# tweeq-STAMP_I2C_PRESSURE_BMP180_v1.net
KiCad netlist of a schematic drawn in EAGLE
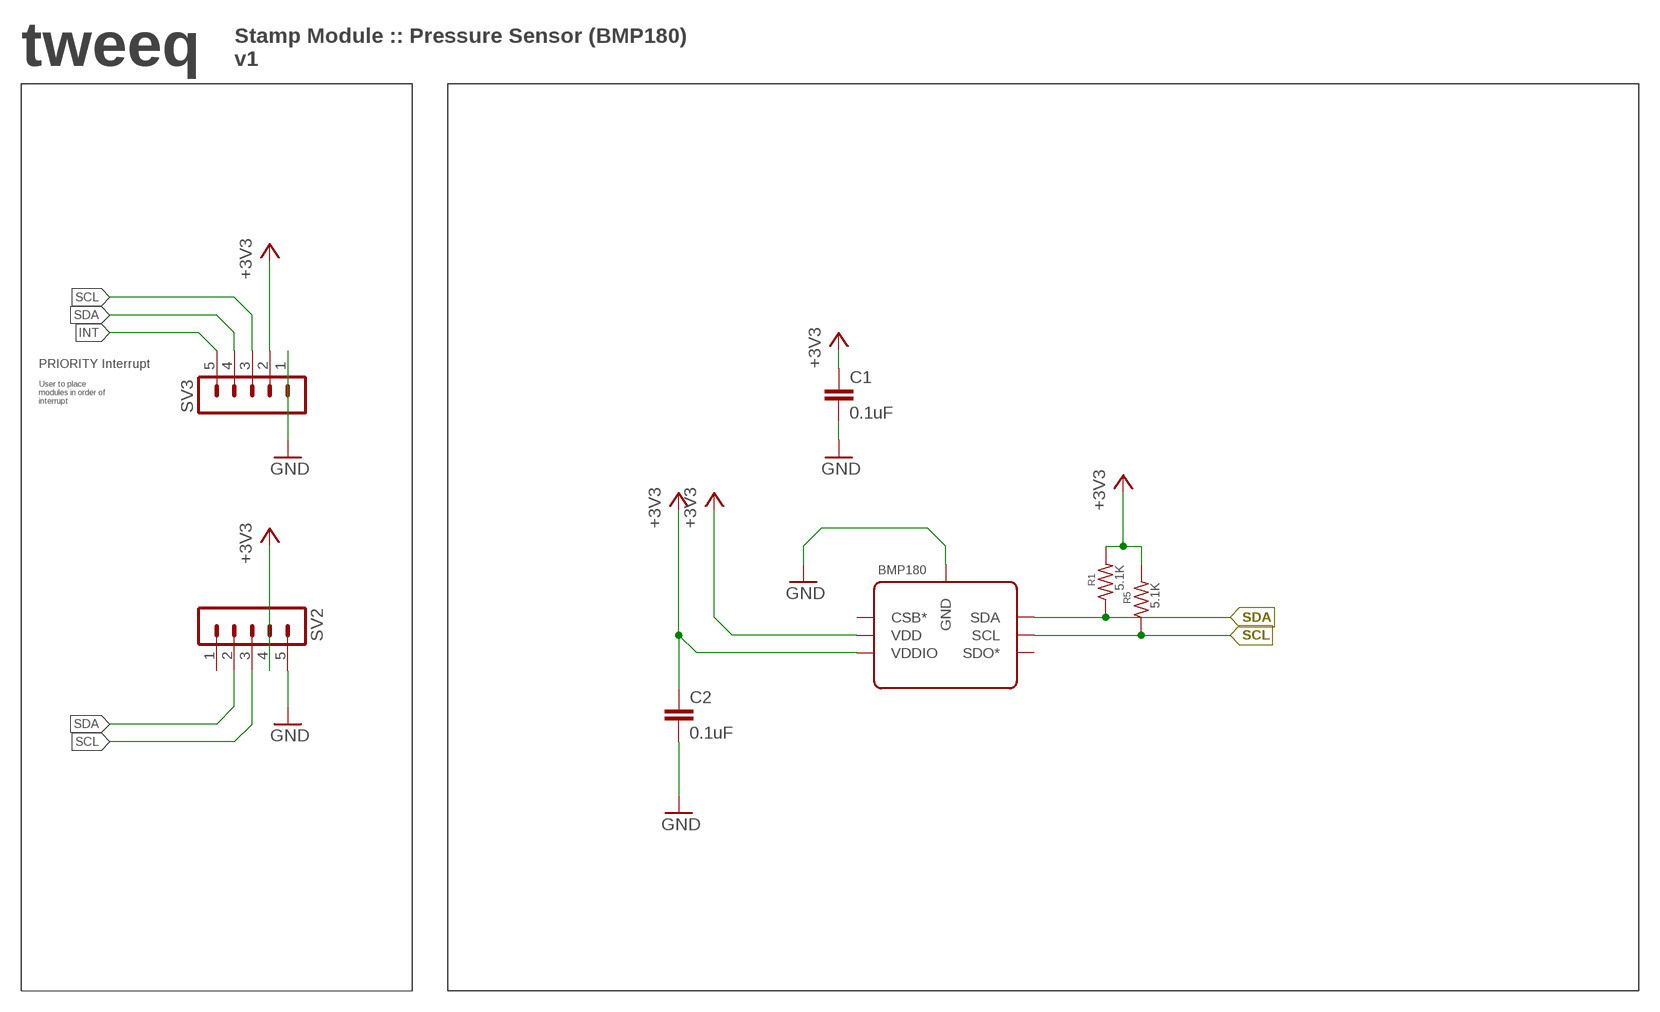
[diagram p0: schematic, sheet 1]

(export (version "E")
  (design (tool "Eeschema 10.0.6"))
  (components
    (comp (ref "BMP180")
      (value "BMP180")
      (footprint "eagle-import:LGA-7PIN")
      (libsource (lib "eagle-import") (part "BMP180"))
    )
    (comp (ref "C1")
      (value "0.1uF")
      (footprint "eagle-import:C0402K")
      (libsource (lib "eagle-import") (part "C-EUC0402K"))
    )
    (comp (ref "C2")
      (value "0.1uF")
      (footprint "eagle-import:C0402K")
      (libsource (lib "eagle-import") (part "C-EUC0402K"))
    )
    (comp (ref "R1")
      (value "5.1K")
      (footprint "eagle-import:R0402")
      (libsource (lib "eagle-import") (part "R-US_R0402"))
    )
    (comp (ref "R5")
      (value "5.1K")
      (footprint "eagle-import:R0402")
      (libsource (lib "eagle-import") (part "R-US_R0402"))
    )
    (comp (ref "SV2")
      (value "M05-1STAMP")
      (footprint "eagle-import:1X05-1.5MM-STAMP")
      (libsource (lib "eagle-import") (part "M05-1STAMP"))
    )
    (comp (ref "SV3")
      (value "M05-1STAMP")
      (footprint "eagle-import:1X05-1.5MM-STAMP")
      (libsource (lib "eagle-import") (part "M05-1STAMP"))
    )
  )
  (nets
    (net (code "1") (name "+3V3") (class "Default")
      (node (ref "BMP180") (pin "2") (pinfunction "VDD_2") (pintype "bidirectional"))
      (node (ref "BMP180") (pin "3") (pinfunction "VDDIO_3") (pintype "bidirectional"))
      (node (ref "C1") (pin "1") (pinfunction "1_1") (pintype "passive"))
      (node (ref "C2") (pin "1") (pinfunction "1_1") (pintype "passive"))
      (node (ref "R1") (pin "2") (pinfunction "2_2") (pintype "passive"))
      (node (ref "R5") (pin "2") (pinfunction "2_2") (pintype "passive"))
      (node (ref "SV2") (pin "4") (pinfunction "4_4") (pintype "passive"))
      (node (ref "SV3") (pin "2") (pinfunction "2_2") (pintype "passive"))
    )
    (net (code "2") (name "GND") (class "Default")
      (node (ref "BMP180") (pin "7") (pinfunction "GND_7") (pintype "bidirectional"))
      (node (ref "C1") (pin "2") (pinfunction "2_2") (pintype "passive"))
      (node (ref "C2") (pin "2") (pinfunction "2_2") (pintype "passive"))
      (node (ref "SV2") (pin "5") (pinfunction "5_5") (pintype "passive"))
      (node (ref "SV3") (pin "1") (pinfunction "1_1") (pintype "passive"))
    )
    (net (code "3") (name "INT") (class "Default")
      (node (ref "SV3") (pin "5") (pinfunction "5_5") (pintype "passive"))
    )
    (net (code "4") (name "SCL") (class "Default")
      (node (ref "BMP180") (pin "5") (pinfunction "SCL_5") (pintype "bidirectional"))
      (node (ref "R5") (pin "1") (pinfunction "1_1") (pintype "passive"))
      (node (ref "SV2") (pin "3") (pinfunction "3_3") (pintype "passive"))
      (node (ref "SV3") (pin "3") (pinfunction "3_3") (pintype "passive"))
    )
    (net (code "5") (name "SDA") (class "Default")
      (node (ref "BMP180") (pin "6") (pinfunction "SDA_6") (pintype "bidirectional"))
      (node (ref "R1") (pin "1") (pinfunction "1_1") (pintype "passive"))
      (node (ref "SV2") (pin "2") (pinfunction "2_2") (pintype "passive"))
      (node (ref "SV3") (pin "4") (pinfunction "4_4") (pintype "passive"))
    )
    (net (code "6") (name "unconnected-(BMP180-CSB*-Pad1)") (class "Default")
      (node (ref "BMP180") (pin "1") (pinfunction "CSB*_1") (pintype "bidirectional"))
    )
    (net (code "7") (name "unconnected-(BMP180-SDO*-Pad4)") (class "Default")
      (node (ref "BMP180") (pin "4") (pinfunction "SDO*_4") (pintype "bidirectional"))
    )
    (net (code "8") (name "unconnected-(SV2-Pad1)") (class "Default")
      (node (ref "SV2") (pin "1") (pinfunction "1_1") (pintype "passive"))
    )
  )
)
